# BOWIE_MCU.net
KiCad netlist of a schematic drawn in Altium Designer
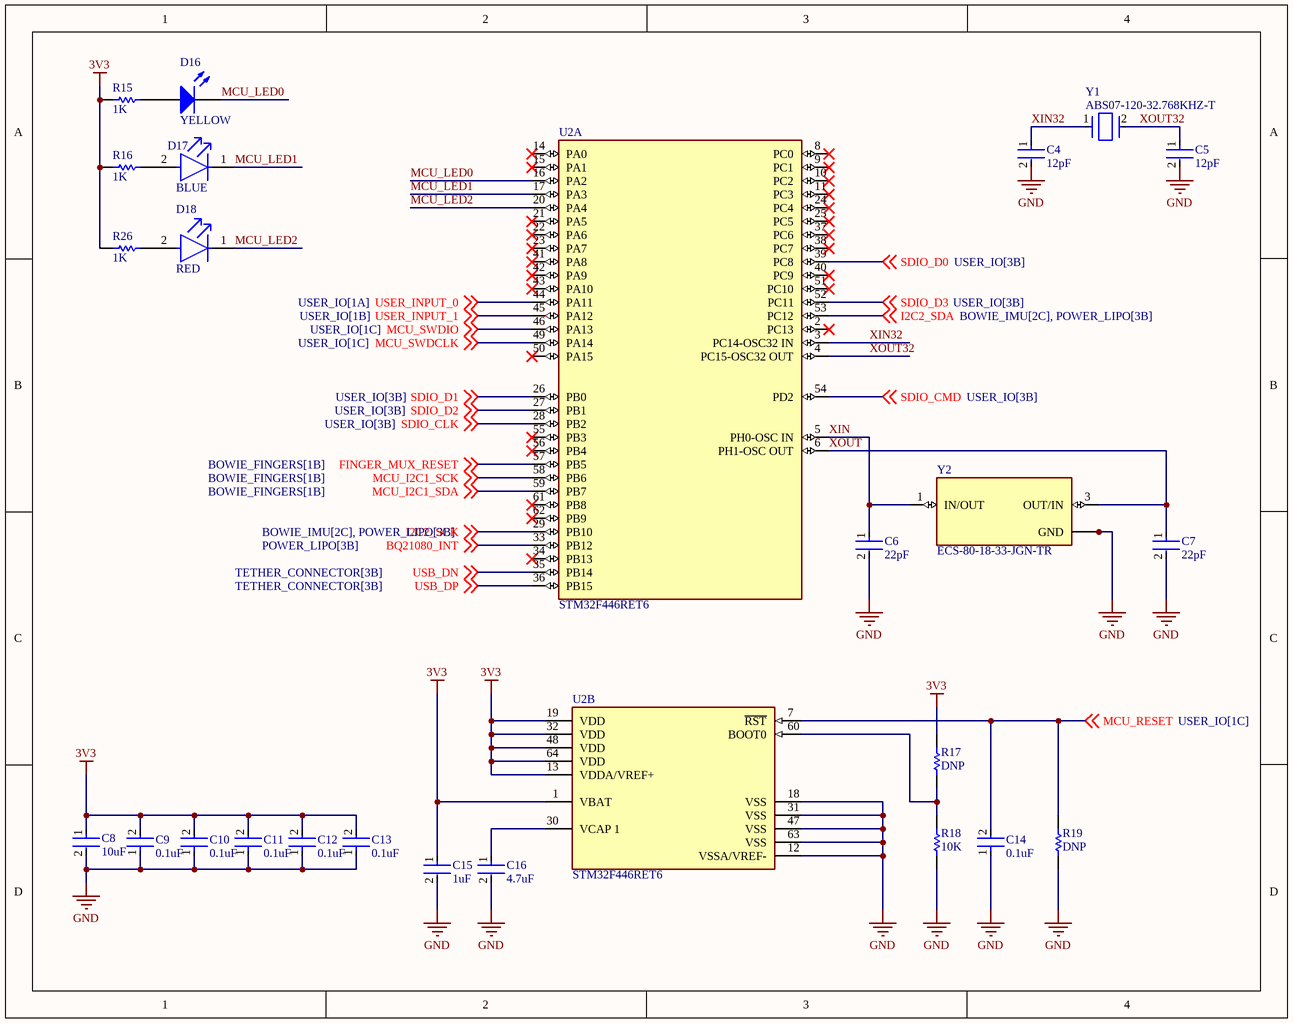
[diagram p0: BOWIE_MCU.SchDoc]

(export (version "E")
  (design (tool "Eeschema 10.0.6"))
  (components
    (comp (ref "C4")
      (value "12pF")
      (footprint "FP-0402-L_1_0_1-W_0_5_0_1-IPC_B")
      (description "General Purpose Ceramic Capacitor, 0402, 12pF, 10%, C0G, 30ppm/°C, 50V")
      (fields (field (name "TOLERANCE") "10%"))
      (libsource (lib "Altium Content Vault") (part "b4654b650e69147ec39a6b967a45e02"))
    )
    (comp (ref "C5")
      (value "12pF")
      (footprint "FP-0402-L_1_0_1-W_0_5_0_1-IPC_B")
      (description "General Purpose Ceramic Capacitor, 0402, 12pF, 10%, C0G, 30ppm/°C, 50V")
      (fields (field (name "TOLERANCE") "10%"))
      (libsource (lib "Altium Content Vault") (part "b4654b650e69147ec39a6b967a45e02"))
    )
    (comp (ref "C6")
      (value "22pF")
      (footprint "FP-0402-L_1_0_1-W_0_5_0_1-MFG")
      (description "General Purpose Ceramic Capacitor, 0402, 22pF, 5%, C0G, 30ppm/°C, 50V")
      (fields (field (name "VOLTAGE") "50V") (field (name "TOLERANCE") "5%"))
      (libsource (lib "Altium Content Vault") (part "b4654b650e69147ec39a6b967a45e02"))
    )
    (comp (ref "C7")
      (value "22pF")
      (footprint "FP-0402-L_1_0_1-W_0_5_0_1-MFG")
      (description "General Purpose Ceramic Capacitor, 0402, 22pF, 5%, C0G, 30ppm/°C, 50V")
      (fields (field (name "VOLTAGE") "50V") (field (name "TOLERANCE") "5%"))
      (libsource (lib "Altium Content Vault") (part "b4654b650e69147ec39a6b967a45e02"))
    )
    (comp (ref "C8")
      (value "10uF")
      (footprint "FP-CL05A106MP5NUNC-MFG")
      (description "CAP CER 10UF 10V X5R 0402")
      (fields
        (field (name "OCTOPART") "https://octopart.com/cl05a106mp5nunc-samsung-22457395")
        (field (name "TOLERANCE") "20%")
      )
      (libsource (lib "Altium Content Vault") (part "b4654b650e69147ec39a6b967a45e02"))
    )
    (comp (ref "C9")
      (value "0.1uF")
      (footprint "FP-CC0201-BA-MFG")
      (description "CAP CER 0.1UF 6.3V X5R 0201")
      (fields (field (name "MANUFACTURER") "Yageo") (field (name "TOLERANCE") "0.1"))
      (libsource (lib "Altium Content Vault") (part "11868f565c42a9108669ba33697ecf6"))
    )
    (comp (ref "C10")
      (value "0.1uF")
      (footprint "FP-CC0201-BA-MFG")
      (description "CAP CER 0.1UF 6.3V X5R 0201")
      (fields (field (name "MANUFACTURER") "Yageo") (field (name "TOLERANCE") "0.1"))
      (libsource (lib "Altium Content Vault") (part "11868f565c42a9108669ba33697ecf6"))
    )
    (comp (ref "C11")
      (value "0.1uF")
      (footprint "FP-CC0201-BA-MFG")
      (description "CAP CER 0.1UF 6.3V X5R 0201")
      (fields (field (name "MANUFACTURER") "Yageo") (field (name "TOLERANCE") "0.1"))
      (libsource (lib "Altium Content Vault") (part "11868f565c42a9108669ba33697ecf6"))
    )
    (comp (ref "C12")
      (value "0.1uF")
      (footprint "FP-CC0201-BA-MFG")
      (description "CAP CER 0.1UF 6.3V X5R 0201")
      (fields (field (name "MANUFACTURER") "Yageo") (field (name "TOLERANCE") "0.1"))
      (libsource (lib "Altium Content Vault") (part "11868f565c42a9108669ba33697ecf6"))
    )
    (comp (ref "C13")
      (value "0.1uF")
      (footprint "FP-CC0201-BA-MFG")
      (description "CAP CER 0.1UF 6.3V X5R 0201")
      (fields (field (name "MANUFACTURER") "Yageo") (field (name "TOLERANCE") "0.1"))
      (libsource (lib "Altium Content Vault") (part "11868f565c42a9108669ba33697ecf6"))
    )
    (comp (ref "C14")
      (value "0.1uF")
      (footprint "FP-CC0201-BA-MFG")
      (description "CAP CER 0.1UF 6.3V X5R 0201")
      (fields (field (name "MANUFACTURER") "Yageo") (field (name "TOLERANCE") "0.1"))
      (libsource (lib "Altium Content Vault") (part "11868f565c42a9108669ba33697ecf6"))
    )
    (comp (ref "C15")
      (value "1uF")
      (footprint "FP-CL511-IPC_C")
      (description "Cap Ceramic 1uF 10V X5R ±10% SMD 0402 +85°C Paper T/R")
      (fields (field (name "TOLERANCE") "10%"))
      (libsource (lib "Altium Content Vault") (part "b4654b650e69147ec39a6b967a45e02"))
    )
    (comp (ref "C16")
      (value "4.7uF")
      (footprint "FP-C1005-050-0_15-MFG")
      (description "CAP CER 4.7UF 10V X5R 0402")
      (fields (field (name "TOLERANCE") "10%"))
      (libsource (lib "Altium Content Vault") (part "b4654b650e69147ec39a6b967a45e02"))
    )
    (comp (ref "D16")
      (value "YELLOW")
      (footprint "0603_A")
      (description "SMD mono-color Chip LED, WL-SMCW, Yellow")
      (fields (field (name "PARTNUMBER") "150060YS75000") (field (name "MANUFACTURER") "Wuerth Elektronik"))
      (libsource (lib "Altium Content Vault") (part "WE-LED_K1A2-2"))
    )
    (comp (ref "D17")
      (value "BLUE")
      (footprint "FP-LTST-C191TBKT-MFG")
      (description "LED BLUE CLEAR CHIP SMD")
      (libsource (lib "Altium Content Vault") (part "8706943c75ba83719d021d2fdc84c58"))
    )
    (comp (ref "D18")
      (value "RED")
      (footprint "FP-SML-P11UTT86-MFG")
      (description "LED RED CLEAR 1006 SMD")
      (libsource (lib "Altium Content Vault") (part "8706943c75ba83719d021d2fdc84c58"))
    )
    (comp (ref "R15")
      (value "1K")
      (footprint "RESC1005X40X25NL05T05")
      (description "Chip Resistor, 1 KOhm, +/- 1%, 100 mW, -55 to 155 degC, 0402 (1005 Metric), RoHS, Tape and Reel")
      (fields (field (name "PARTNUMBER") "ERJ-2RKF1001X") (field (name "MANUFACTURER") "Basic Passives"))
      (libsource (lib "Altium Content Vault") (part "RES-2"))
    )
    (comp (ref "R16")
      (value "1K")
      (footprint "RESC1005X40X25NL05T05")
      (description "Chip Resistor, 1 KOhm, +/- 1%, 100 mW, -55 to 155 degC, 0402 (1005 Metric), RoHS, Tape and Reel")
      (fields (field (name "PARTNUMBER") "ERJ-2RKF1001X") (field (name "MANUFACTURER") "Basic Passives"))
      (libsource (lib "Altium Content Vault") (part "RES-2"))
    )
    (comp (ref "R17")
      (value "DNP")
      (footprint "RESC1005X40X25ML05T10")
      (fields (field (name "PART NUMBER") "CRCW040210K0FKEDHP") (field (name "MANUFACTURER") "Vishay Dale"))
      (libsource (lib "Altium Content Vault") (part "RES"))
    )
    (comp (ref "R18")
      (value "10K")
      (footprint "RESC1005X40X25ML05T10")
      (fields (field (name "PART NUMBER") "CRCW040210K0FKEDHP") (field (name "MANUFACTURER") "Vishay Dale"))
      (libsource (lib "Altium Content Vault") (part "RES"))
    )
    (comp (ref "R19")
      (value "DNP")
      (footprint "RESC1005X40X25NL05T10")
      (fields (field (name "MANUFACTURER") "Yageo / Phycomp") (field (name "PART NUMBER") "RC0402JR-070RL"))
      (libsource (lib "Altium Content Vault") (part "RES"))
    )
    (comp (ref "R26")
      (value "1K")
      (footprint "RESC1005X40X25NL05T05")
      (description "Chip Resistor, 1 KOhm, +/- 1%, 100 mW, -55 to 155 degC, 0402 (1005 Metric), RoHS, Tape and Reel")
      (fields (field (name "PARTNUMBER") "ERJ-2RKF1001X") (field (name "MANUFACTURER") "Basic Passives"))
      (libsource (lib "Altium Content Vault") (part "RES-2"))
    )
    (comp (ref "U2")
      (value "STM32F446RET6")
      (footprint "FP-LQFP64-5W-MFG")
      (description "IC MCU 32BIT 512KB FLASH 64LQFP")
      (fields
        (field (name "OCTOPART") "https://octopart.com/stm32f446ret6-stmicroelectronics-52642920")
        (field (name "MANUFACTURER") "ST")
      )
      (libsource (lib "Altium Content Vault") (part "ee11adc32c0ab33b933cccf4348c338"))
    )
    (comp (ref "Y1")
      (value "ABS07-120-32.768KHZ-T")
      (footprint "FP-ABS07-120-MFG")
      (description "CRYSTAL 32.7680KHZ 6PF SMD")
      (fields (field (name "TOLERANCE") "20ppm"))
      (libsource (lib "Altium Content Vault") (part "c23a69dc6c9e2f18f2079038eb95dd1"))
    )
    (comp (ref "Y2")
      (value "ECS-80-18-33-JGN-TR")
      (footprint "ECS-80-18-33-JGN-TR:XTAL_ECS-240-8-33-AGN-TR")
      (fields (field (name "MF") "{'manufacturer': u'ECS Inc.'}"))
      (libsource (lib "*") (part "ECS-80-18-33-JGN-TR"))
    )
  )
  (nets
    (net (code "1") (name "/MCU_LED0") (class "Default")
      (node (ref "D16") (pin "1") (pinfunction "K_1") (pintype "passive"))
      (node (ref "U2") (pin "16") (pinfunction "PA2_16") (pintype "bidirectional"))
    )
    (net (code "2") (name "/MCU_LED1") (class "Default")
      (node (ref "D17") (pin "1") (pinfunction "C_1") (pintype "passive"))
      (node (ref "U2") (pin "17") (pinfunction "PA3_17") (pintype "bidirectional"))
    )
    (net (code "3") (name "/MCU_LED2") (class "Default")
      (node (ref "D18") (pin "1") (pinfunction "C_1") (pintype "passive"))
      (node (ref "U2") (pin "20") (pinfunction "PA4_20") (pintype "bidirectional"))
    )
    (net (code "4") (name "/XIN") (class "Default")
      (node (ref "C6") (pin "1") (pinfunction "1_1") (pintype "passive"))
      (node (ref "U2") (pin "5") (pinfunction "PH0-OSC_IN_5") (pintype "bidirectional"))
      (node (ref "Y2") (pin "1") (pinfunction "IN/OUT_1") (pintype "bidirectional"))
    )
    (net (code "5") (name "/XIN32") (class "Default")
      (node (ref "C4") (pin "1") (pinfunction "1_1") (pintype "passive"))
      (node (ref "U2") (pin "3") (pinfunction "PC14-OSC32_IN_3") (pintype "bidirectional"))
      (node (ref "Y1") (pin "1") (pinfunction "1_1") (pintype "passive"))
    )
    (net (code "6") (name "/XOUT") (class "Default")
      (node (ref "C7") (pin "1") (pinfunction "1_1") (pintype "passive"))
      (node (ref "U2") (pin "6") (pinfunction "PH1-OSC_OUT_6") (pintype "bidirectional"))
      (node (ref "Y2") (pin "3") (pinfunction "OUT/IN_3") (pintype "bidirectional"))
    )
    (net (code "7") (name "/XOUT32") (class "Default")
      (node (ref "C5") (pin "1") (pinfunction "1_1") (pintype "passive"))
      (node (ref "U2") (pin "4") (pinfunction "PC15-OSC32_OUT_4") (pintype "bidirectional"))
      (node (ref "Y1") (pin "2") (pinfunction "2_2") (pintype "passive"))
    )
    (net (code "8") (name "3V3") (class "Default")
      (node (ref "C10") (pin "2") (pinfunction "2_2") (pintype "passive"))
      (node (ref "C11") (pin "2") (pinfunction "2_2") (pintype "passive"))
      (node (ref "C12") (pin "2") (pinfunction "2_2") (pintype "passive"))
      (node (ref "C13") (pin "2") (pinfunction "2_2") (pintype "passive"))
      (node (ref "C15") (pin "1") (pinfunction "1_1") (pintype "passive"))
      (node (ref "C8") (pin "1") (pinfunction "1_1") (pintype "passive"))
      (node (ref "C9") (pin "2") (pinfunction "2_2") (pintype "passive"))
      (node (ref "R15") (pin "1") (pinfunction "1_1") (pintype "passive"))
      (node (ref "R16") (pin "1") (pinfunction "1_1") (pintype "passive"))
      (node (ref "R17") (pin "2") (pinfunction "2_2") (pintype "passive"))
      (node (ref "R26") (pin "1") (pinfunction "1_1") (pintype "passive"))
      (node (ref "U2") (pin "1") (pinfunction "VBAT_1") (pintype "power_in"))
      (node (ref "U2") (pin "13") (pinfunction "VDDA/VREF+_13") (pintype "power_in"))
      (node (ref "U2") (pin "19") (pinfunction "VDD_19") (pintype "power_in"))
      (node (ref "U2") (pin "32") (pinfunction "VDD_32") (pintype "power_in"))
      (node (ref "U2") (pin "48") (pinfunction "VDD_48") (pintype "power_in"))
      (node (ref "U2") (pin "64") (pinfunction "VDD_64") (pintype "power_in"))
    )
    (net (code "9") (name "BQ21080_INT") (class "Default")
      (node (ref "U2") (pin "33") (pinfunction "PB12_33") (pintype "bidirectional"))
    )
    (net (code "10") (name "FINGER_MUX_RESET") (class "Default")
      (node (ref "U2") (pin "57") (pinfunction "PB5_57") (pintype "bidirectional"))
    )
    (net (code "11") (name "GND") (class "Default")
      (node (ref "C10") (pin "1") (pinfunction "1_1") (pintype "passive"))
      (node (ref "C11") (pin "1") (pinfunction "1_1") (pintype "passive"))
      (node (ref "C12") (pin "1") (pinfunction "1_1") (pintype "passive"))
      (node (ref "C13") (pin "1") (pinfunction "1_1") (pintype "passive"))
      (node (ref "C14") (pin "1") (pinfunction "1_1") (pintype "passive"))
      (node (ref "C15") (pin "2") (pinfunction "2_2") (pintype "passive"))
      (node (ref "C16") (pin "2") (pinfunction "2_2") (pintype "passive"))
      (node (ref "C4") (pin "2") (pinfunction "2_2") (pintype "passive"))
      (node (ref "C5") (pin "2") (pinfunction "2_2") (pintype "passive"))
      (node (ref "C6") (pin "2") (pinfunction "2_2") (pintype "passive"))
      (node (ref "C7") (pin "2") (pinfunction "2_2") (pintype "passive"))
      (node (ref "C8") (pin "2") (pinfunction "2_2") (pintype "passive"))
      (node (ref "C9") (pin "1") (pinfunction "1_1") (pintype "passive"))
      (node (ref "R18") (pin "1") (pinfunction "1_1") (pintype "passive"))
      (node (ref "R19") (pin "1") (pinfunction "1_1") (pintype "passive"))
      (node (ref "U2") (pin "12") (pinfunction "VSSA/VREF-_12") (pintype "power_in"))
      (node (ref "U2") (pin "18") (pinfunction "VSS_18") (pintype "power_in"))
      (node (ref "U2") (pin "31") (pinfunction "VSS_31") (pintype "power_in"))
      (node (ref "U2") (pin "47") (pinfunction "VSS_47") (pintype "power_in"))
      (node (ref "U2") (pin "63") (pinfunction "VSS_63") (pintype "power_in"))
      (node (ref "Y2") (pin "2") (pinfunction "GND_2") (pintype "power_in"))
      (node (ref "Y2") (pin "4") (pinfunction "GND_4") (pintype "power_in"))
    )
    (net (code "12") (name "I2C2_SCK") (class "Default")
      (node (ref "U2") (pin "29") (pinfunction "PB10_29") (pintype "bidirectional"))
    )
    (net (code "13") (name "I2C2_SDA") (class "Default")
      (node (ref "U2") (pin "53") (pinfunction "PC12_53") (pintype "bidirectional"))
    )
    (net (code "14") (name "MCU_I2C1_SCK") (class "Default")
      (node (ref "U2") (pin "58") (pinfunction "PB6_58") (pintype "bidirectional"))
    )
    (net (code "15") (name "MCU_I2C1_SDA") (class "Default")
      (node (ref "U2") (pin "59") (pinfunction "PB7_59") (pintype "bidirectional"))
    )
    (net (code "16") (name "MCU_RESET") (class "Default")
      (node (ref "C14") (pin "2") (pinfunction "2_2") (pintype "passive"))
      (node (ref "R19") (pin "2") (pinfunction "2_2") (pintype "passive"))
      (node (ref "U2") (pin "7") (pinfunction "~{RST}_7") (pintype "input"))
    )
    (net (code "17") (name "MCU_SWDCLK") (class "Default")
      (node (ref "U2") (pin "49") (pinfunction "PA14_49") (pintype "bidirectional"))
    )
    (net (code "18") (name "MCU_SWDIO") (class "Default")
      (node (ref "U2") (pin "46") (pinfunction "PA13_46") (pintype "bidirectional"))
    )
    (net (code "19") (name "Net-(D16-A)") (class "Default")
      (node (ref "D16") (pin "2") (pinfunction "A_2") (pintype "passive"))
      (node (ref "R15") (pin "2") (pinfunction "2_2") (pintype "passive"))
    )
    (net (code "20") (name "Net-(D17-A)") (class "Default")
      (node (ref "D17") (pin "2") (pinfunction "A_2") (pintype "passive"))
      (node (ref "R16") (pin "2") (pinfunction "2_2") (pintype "passive"))
    )
    (net (code "21") (name "Net-(D18-A)") (class "Default")
      (node (ref "D18") (pin "2") (pinfunction "A_2") (pintype "passive"))
      (node (ref "R26") (pin "2") (pinfunction "2_2") (pintype "passive"))
    )
    (net (code "22") (name "Net-(U2B-BOOT0)") (class "Default")
      (node (ref "R17") (pin "1") (pinfunction "1_1") (pintype "passive"))
      (node (ref "R18") (pin "2") (pinfunction "2_2") (pintype "passive"))
      (node (ref "U2") (pin "60") (pinfunction "BOOT0_60") (pintype "input"))
    )
    (net (code "23") (name "Net-(U2B-VCAP_1)") (class "Default")
      (node (ref "C16") (pin "1") (pinfunction "1_1") (pintype "passive"))
      (node (ref "U2") (pin "30") (pinfunction "VCAP_1_30") (pintype "power_in"))
    )
    (net (code "24") (name "SDIO_CLK") (class "Default")
      (node (ref "U2") (pin "28") (pinfunction "PB2_28") (pintype "bidirectional"))
    )
    (net (code "25") (name "SDIO_CMD") (class "Default")
      (node (ref "U2") (pin "54") (pinfunction "PD2_54") (pintype "bidirectional"))
    )
    (net (code "26") (name "SDIO_D0") (class "Default")
      (node (ref "U2") (pin "39") (pinfunction "PC8_39") (pintype "bidirectional"))
    )
    (net (code "27") (name "SDIO_D1") (class "Default")
      (node (ref "U2") (pin "26") (pinfunction "PB0_26") (pintype "bidirectional"))
    )
    (net (code "28") (name "SDIO_D2") (class "Default")
      (node (ref "U2") (pin "27") (pinfunction "PB1_27") (pintype "bidirectional"))
    )
    (net (code "29") (name "SDIO_D3") (class "Default")
      (node (ref "U2") (pin "52") (pinfunction "PC11_52") (pintype "bidirectional"))
    )
    (net (code "30") (name "USB_DN") (class "Default")
      (node (ref "U2") (pin "35") (pinfunction "PB14_35") (pintype "bidirectional"))
    )
    (net (code "31") (name "USB_DP") (class "Default")
      (node (ref "U2") (pin "36") (pinfunction "PB15_36") (pintype "bidirectional"))
    )
    (net (code "32") (name "USER_INPUT_0") (class "Default")
      (node (ref "U2") (pin "44") (pinfunction "PA11_44") (pintype "bidirectional"))
    )
    (net (code "33") (name "USER_INPUT_1") (class "Default")
      (node (ref "U2") (pin "45") (pinfunction "PA12_45") (pintype "bidirectional"))
    )
    (net (code "34") (name "unconnected-(U2A-PA0-Pad14)") (class "Default")
      (node (ref "U2") (pin "14") (pinfunction "PA0_14") (pintype "bidirectional+no_connect"))
    )
    (net (code "35") (name "unconnected-(U2A-PA1-Pad15)") (class "Default")
      (node (ref "U2") (pin "15") (pinfunction "PA1_15") (pintype "bidirectional+no_connect"))
    )
    (net (code "36") (name "unconnected-(U2A-PA5-Pad21)") (class "Default")
      (node (ref "U2") (pin "21") (pinfunction "PA5_21") (pintype "bidirectional+no_connect"))
    )
    (net (code "37") (name "unconnected-(U2A-PA6-Pad22)") (class "Default")
      (node (ref "U2") (pin "22") (pinfunction "PA6_22") (pintype "bidirectional+no_connect"))
    )
    (net (code "38") (name "unconnected-(U2A-PA7-Pad23)") (class "Default")
      (node (ref "U2") (pin "23") (pinfunction "PA7_23") (pintype "bidirectional+no_connect"))
    )
    (net (code "39") (name "unconnected-(U2A-PA8-Pad41)") (class "Default")
      (node (ref "U2") (pin "41") (pinfunction "PA8_41") (pintype "bidirectional+no_connect"))
    )
    (net (code "40") (name "unconnected-(U2A-PA9-Pad42)") (class "Default")
      (node (ref "U2") (pin "42") (pinfunction "PA9_42") (pintype "bidirectional+no_connect"))
    )
    (net (code "41") (name "unconnected-(U2A-PA10-Pad43)") (class "Default")
      (node (ref "U2") (pin "43") (pinfunction "PA10_43") (pintype "bidirectional+no_connect"))
    )
    (net (code "42") (name "unconnected-(U2A-PA15-Pad50)") (class "Default")
      (node (ref "U2") (pin "50") (pinfunction "PA15_50") (pintype "bidirectional+no_connect"))
    )
    (net (code "43") (name "unconnected-(U2A-PB3-Pad55)") (class "Default")
      (node (ref "U2") (pin "55") (pinfunction "PB3_55") (pintype "bidirectional+no_connect"))
    )
    (net (code "44") (name "unconnected-(U2A-PB4-Pad56)") (class "Default")
      (node (ref "U2") (pin "56") (pinfunction "PB4_56") (pintype "bidirectional+no_connect"))
    )
    (net (code "45") (name "unconnected-(U2A-PB8-Pad61)") (class "Default")
      (node (ref "U2") (pin "61") (pinfunction "PB8_61") (pintype "bidirectional+no_connect"))
    )
    (net (code "46") (name "unconnected-(U2A-PB9-Pad62)") (class "Default")
      (node (ref "U2") (pin "62") (pinfunction "PB9_62") (pintype "bidirectional+no_connect"))
    )
    (net (code "47") (name "unconnected-(U2A-PB13-Pad34)") (class "Default")
      (node (ref "U2") (pin "34") (pinfunction "PB13_34") (pintype "bidirectional+no_connect"))
    )
    (net (code "48") (name "unconnected-(U2A-PC0-Pad8)") (class "Default")
      (node (ref "U2") (pin "8") (pinfunction "PC0_8") (pintype "bidirectional+no_connect"))
    )
    (net (code "49") (name "unconnected-(U2A-PC1-Pad9)") (class "Default")
      (node (ref "U2") (pin "9") (pinfunction "PC1_9") (pintype "bidirectional+no_connect"))
    )
    (net (code "50") (name "unconnected-(U2A-PC2-Pad10)") (class "Default")
      (node (ref "U2") (pin "10") (pinfunction "PC2_10") (pintype "bidirectional+no_connect"))
    )
    (net (code "51") (name "unconnected-(U2A-PC3-Pad11)") (class "Default")
      (node (ref "U2") (pin "11") (pinfunction "PC3_11") (pintype "bidirectional+no_connect"))
    )
    (net (code "52") (name "unconnected-(U2A-PC4-Pad24)") (class "Default")
      (node (ref "U2") (pin "24") (pinfunction "PC4_24") (pintype "bidirectional+no_connect"))
    )
    (net (code "53") (name "unconnected-(U2A-PC5-Pad25)") (class "Default")
      (node (ref "U2") (pin "25") (pinfunction "PC5_25") (pintype "bidirectional+no_connect"))
    )
    (net (code "54") (name "unconnected-(U2A-PC6-Pad37)") (class "Default")
      (node (ref "U2") (pin "37") (pinfunction "PC6_37") (pintype "bidirectional+no_connect"))
    )
    (net (code "55") (name "unconnected-(U2A-PC7-Pad38)") (class "Default")
      (node (ref "U2") (pin "38") (pinfunction "PC7_38") (pintype "bidirectional+no_connect"))
    )
    (net (code "56") (name "unconnected-(U2A-PC9-Pad40)") (class "Default")
      (node (ref "U2") (pin "40") (pinfunction "PC9_40") (pintype "bidirectional+no_connect"))
    )
    (net (code "57") (name "unconnected-(U2A-PC10-Pad51)") (class "Default")
      (node (ref "U2") (pin "51") (pinfunction "PC10_51") (pintype "bidirectional+no_connect"))
    )
    (net (code "58") (name "unconnected-(U2A-PC13-Pad2)") (class "Default")
      (node (ref "U2") (pin "2") (pinfunction "PC13_2") (pintype "bidirectional+no_connect"))
    )
  )
)
